# solar_tester.net
KiCad netlist of a schematic drawn in EAGLE
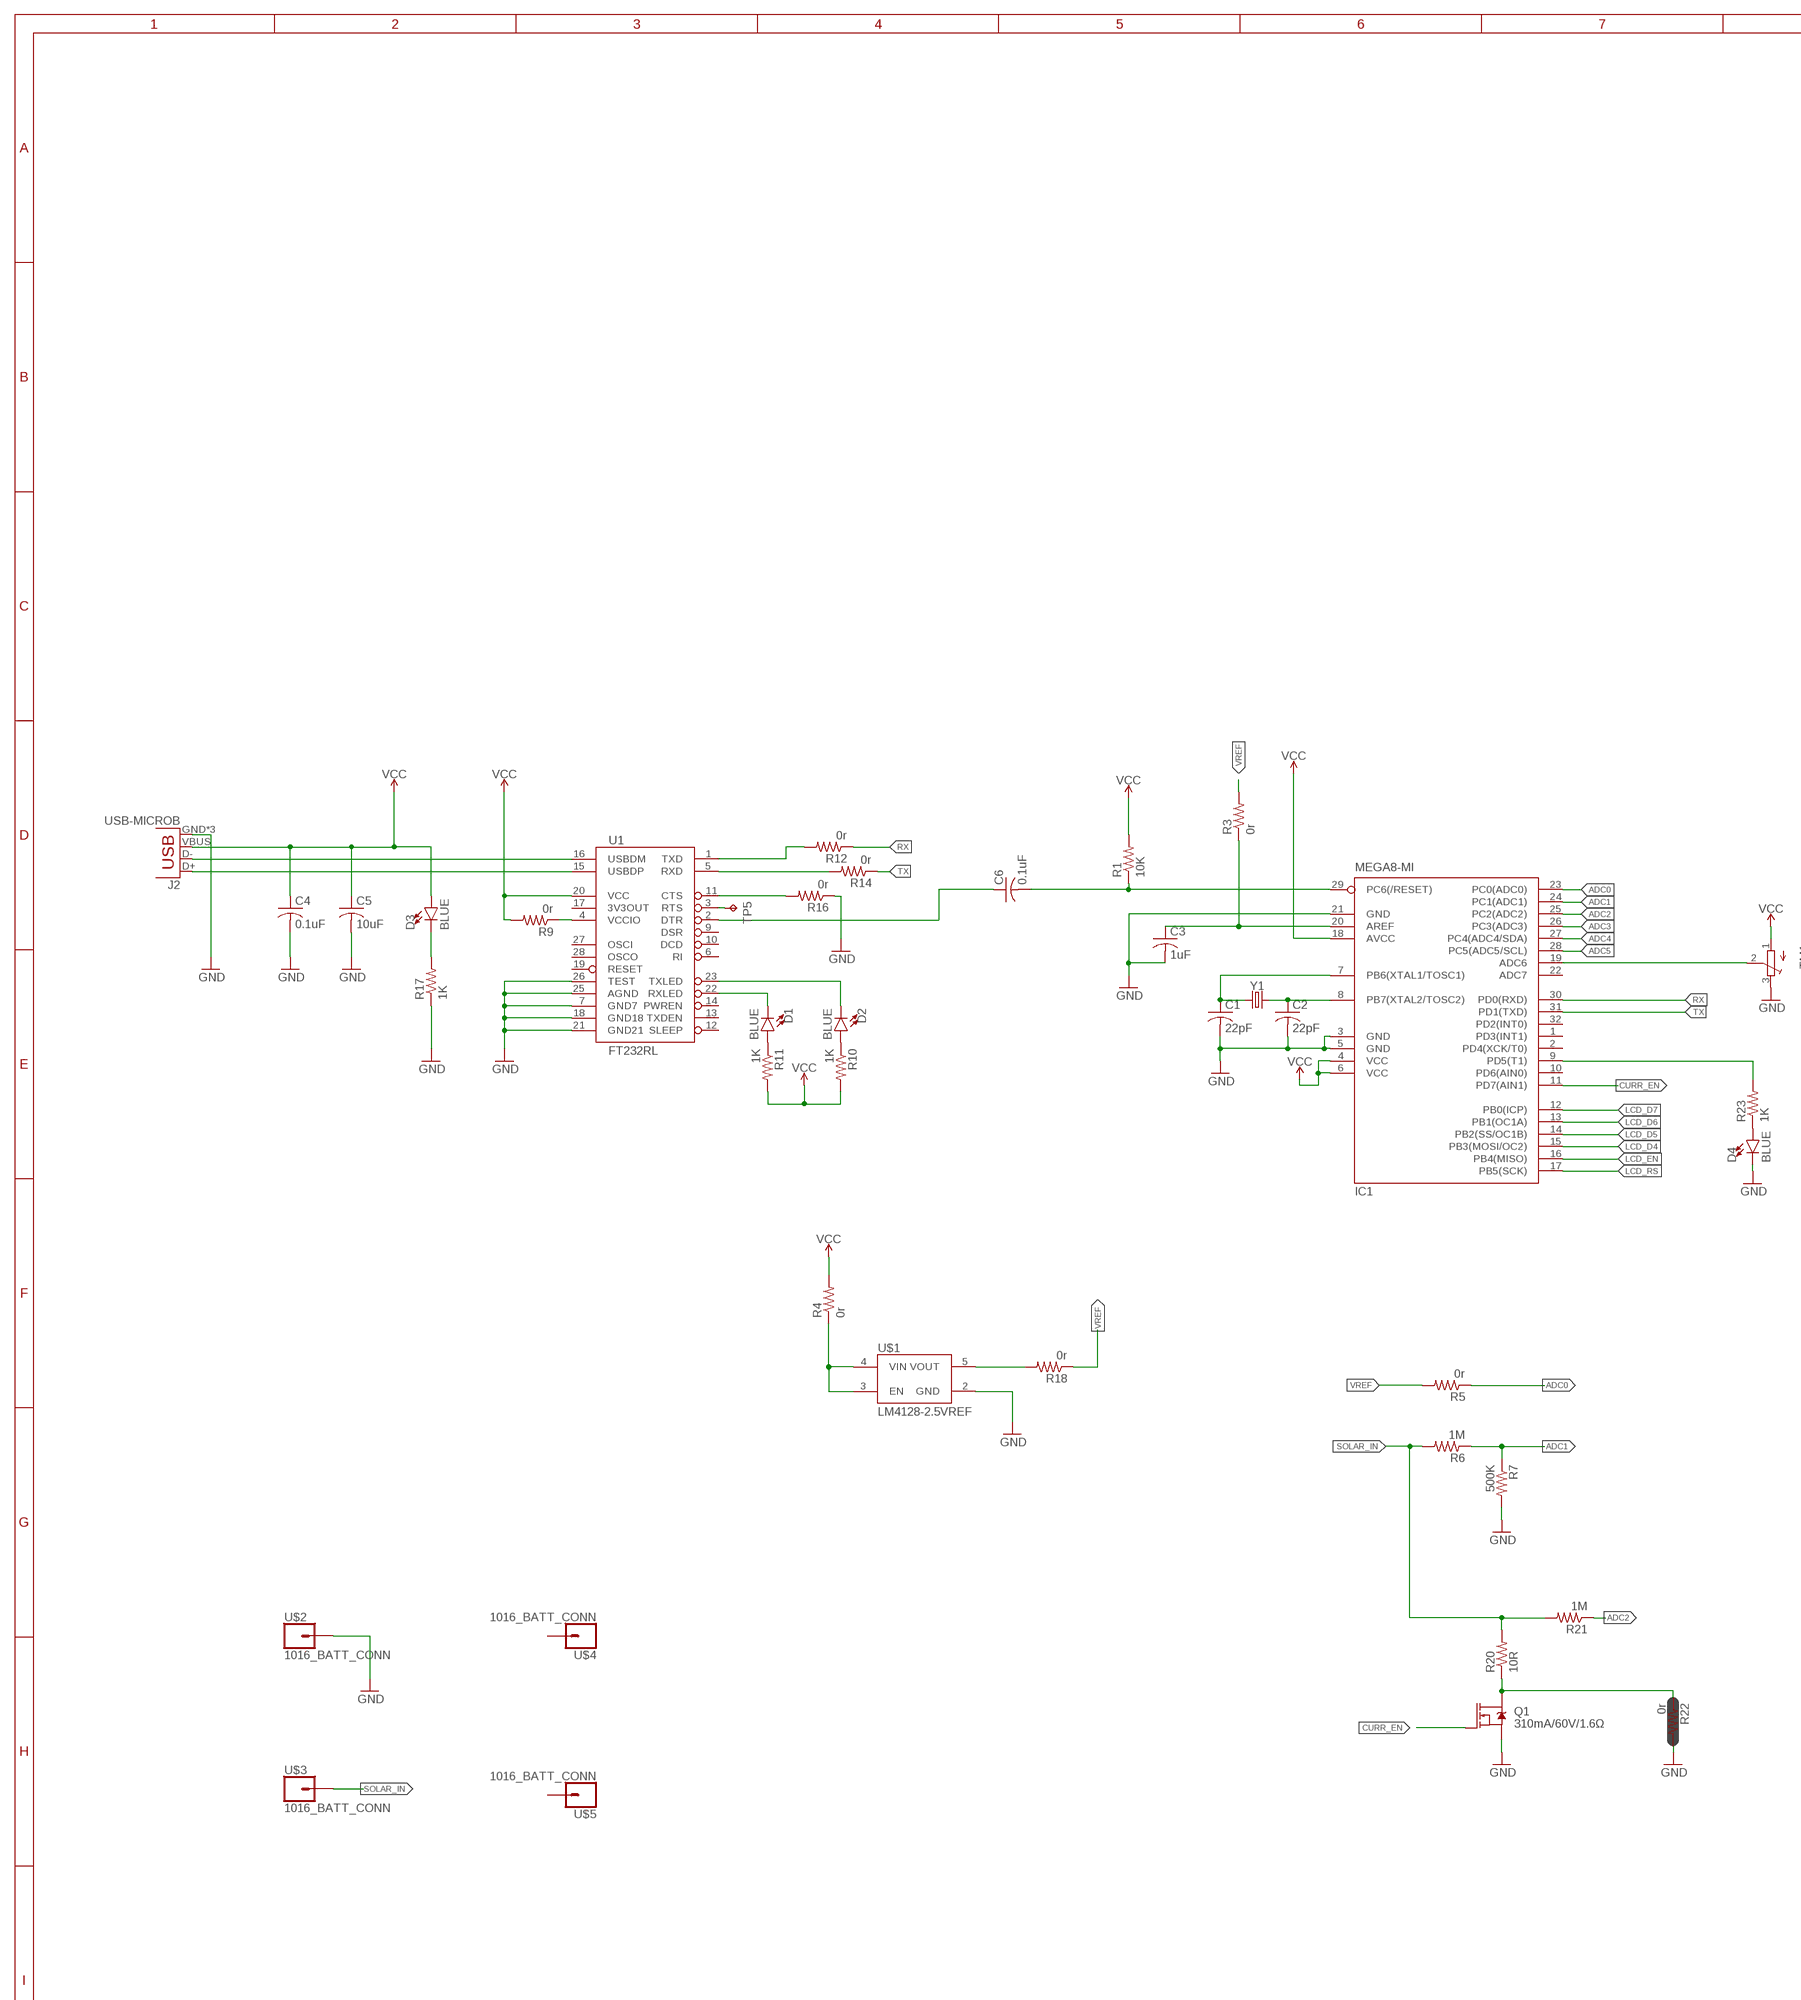
[diagram p0: schematic, sheet 1, part 1 of 2]
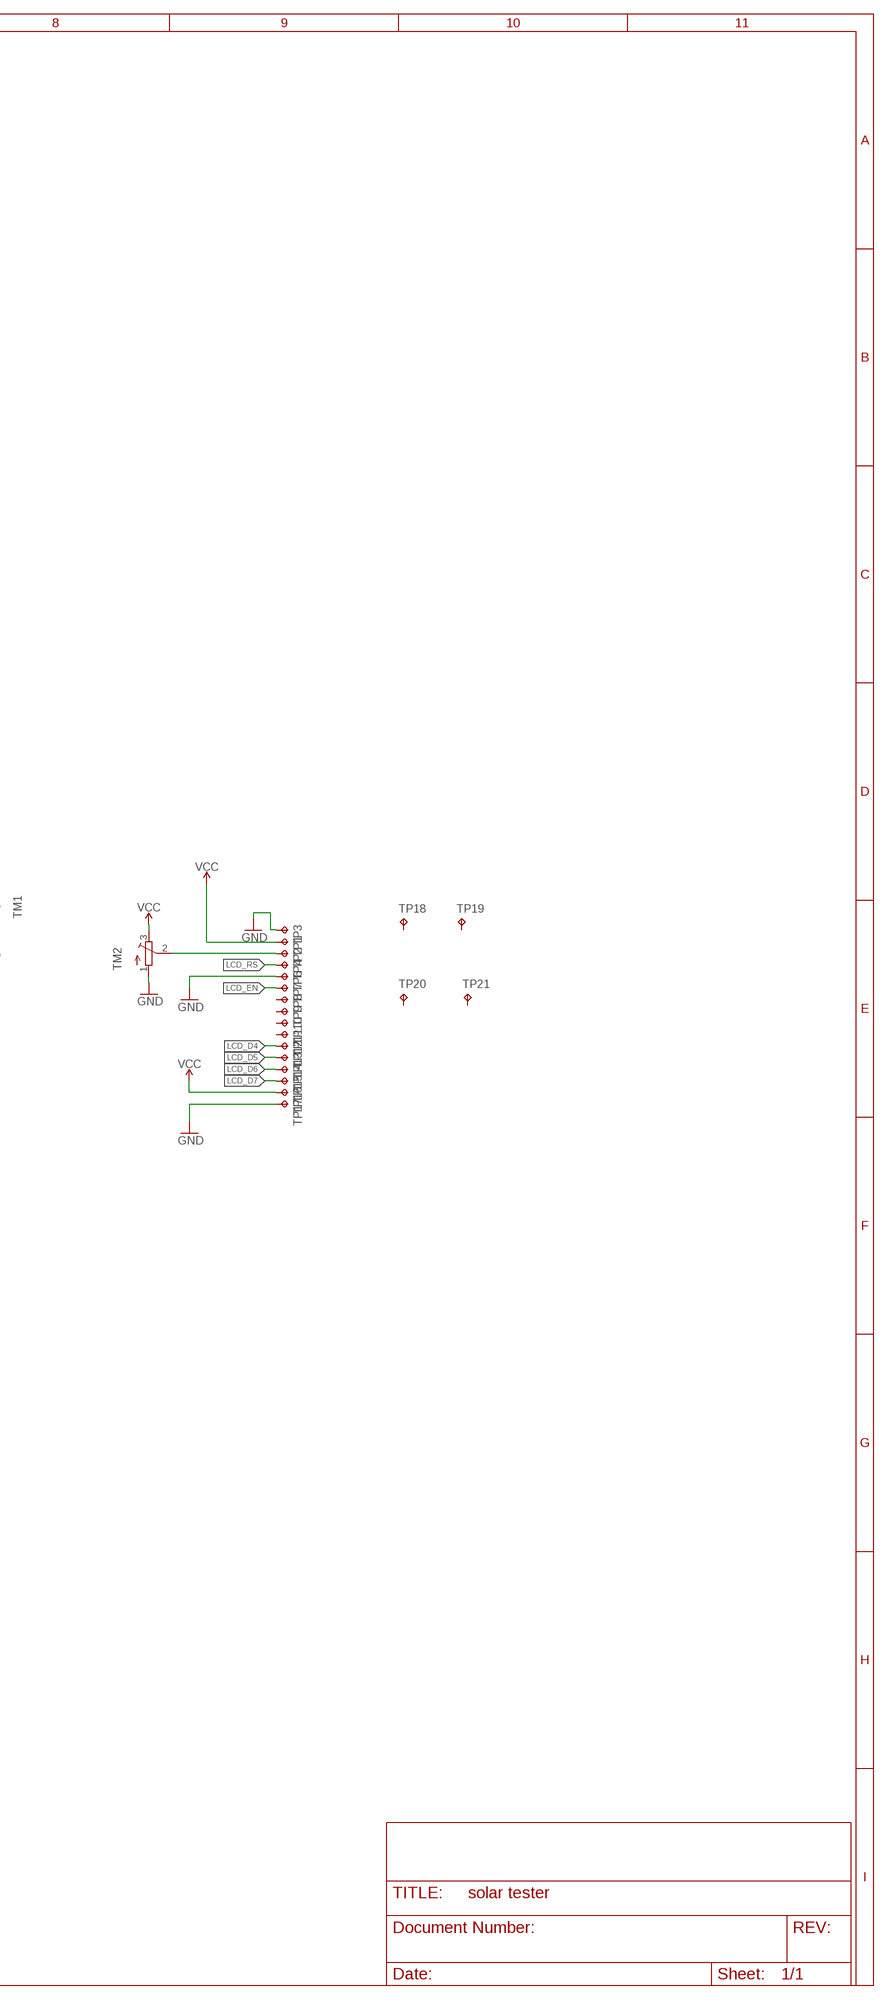
[diagram p1: schematic, sheet 1, part 2 of 2]

(export (version "E")
  (design (tool "Eeschema 10.0.6"))
  (components
    (comp (ref "C1")
      (value "22pF")
      (footprint "eagle-import:C0402")
      (libsource (lib "eagle-import") (part "C-USC0402"))
    )
    (comp (ref "C2")
      (value "22pF")
      (footprint "eagle-import:C0402")
      (libsource (lib "eagle-import") (part "C-USC0402"))
    )
    (comp (ref "C3")
      (value "1uF")
      (footprint "eagle-import:C0402")
      (libsource (lib "eagle-import") (part "C-USC0402"))
    )
    (comp (ref "C4")
      (value "0.1uF")
      (footprint "eagle-import:C0402")
      (libsource (lib "eagle-import") (part "C-USC0402"))
    )
    (comp (ref "C5")
      (value "10uF")
      (footprint "eagle-import:C0402")
      (libsource (lib "eagle-import") (part "C-USC0402"))
    )
    (comp (ref "C6")
      (value "0.1uF")
      (footprint "eagle-import:C0402")
      (libsource (lib "eagle-import") (part "C-USC0402"))
    )
    (comp (ref "D1")
      (value "BLUE")
      (footprint "eagle-import:LED-0603")
      (libsource (lib "eagle-import") (part "LED-BLUE0603"))
    )
    (comp (ref "D2")
      (value "BLUE")
      (footprint "eagle-import:LED-0603")
      (libsource (lib "eagle-import") (part "LED-BLUE0603"))
    )
    (comp (ref "D3")
      (value "BLUE")
      (footprint "eagle-import:LED-0603")
      (libsource (lib "eagle-import") (part "LED-BLUE0603"))
    )
    (comp (ref "D4")
      (value "BLUE")
      (footprint "eagle-import:LED-0603")
      (libsource (lib "eagle-import") (part "LED-BLUE0603"))
    )
    (comp (ref "IC1")
      (value "MEGA8-MI")
      (footprint "eagle-import:MLF32")
      (fields (field (name "MPN") "ATMEGA88PA-MU"))
      (libsource (lib "eagle-import") (part "MEGA8-MI"))
    )
    (comp (ref "J2")
      (value "USB-MICROB")
      (footprint "eagle-import:USB-MICROB")
      (libsource (lib "eagle-import") (part "USB-MICROB"))
    )
    (comp (ref "Q1")
      (value "310mA/60V/1.6Ω")
      (footprint "eagle-import:SOT323")
      (libsource (lib "eagle-import") (part "MOSFET-NCH-2N7002PW"))
    )
    (comp (ref "R1")
      (value "10K")
      (footprint "eagle-import:R0402")
      (libsource (lib "eagle-import") (part "R-US_R0402"))
    )
    (comp (ref "R3")
      (value "0r")
      (footprint "eagle-import:R0402")
      (libsource (lib "eagle-import") (part "R-US_R0402"))
    )
    (comp (ref "R4")
      (value "0r")
      (footprint "eagle-import:R0402")
      (libsource (lib "eagle-import") (part "R-US_R0402"))
    )
    (comp (ref "R5")
      (value "0r")
      (footprint "eagle-import:R0402")
      (libsource (lib "eagle-import") (part "R-US_R0402"))
    )
    (comp (ref "R6")
      (value "1M")
      (footprint "eagle-import:R0402")
      (libsource (lib "eagle-import") (part "R-US_R0402"))
    )
    (comp (ref "R7")
      (value "500K")
      (footprint "eagle-import:R0402")
      (libsource (lib "eagle-import") (part "R-US_R0402"))
    )
    (comp (ref "R9")
      (value "0r")
      (footprint "eagle-import:R0402")
      (libsource (lib "eagle-import") (part "R-US_R0402"))
    )
    (comp (ref "R10")
      (value "1K")
      (footprint "eagle-import:R0402")
      (libsource (lib "eagle-import") (part "R-US_R0402"))
    )
    (comp (ref "R11")
      (value "1K")
      (footprint "eagle-import:R0402")
      (libsource (lib "eagle-import") (part "R-US_R0402"))
    )
    (comp (ref "R12")
      (value "0r")
      (footprint "eagle-import:R0402")
      (libsource (lib "eagle-import") (part "R-US_R0402"))
    )
    (comp (ref "R14")
      (value "0r")
      (footprint "eagle-import:R0402")
      (libsource (lib "eagle-import") (part "R-US_R0402"))
    )
    (comp (ref "R16")
      (value "0r")
      (footprint "eagle-import:R0402")
      (libsource (lib "eagle-import") (part "R-US_R0402"))
    )
    (comp (ref "R17")
      (value "1K")
      (footprint "eagle-import:R0402")
      (libsource (lib "eagle-import") (part "R-US_R0402"))
    )
    (comp (ref "R18")
      (value "0r")
      (footprint "eagle-import:R0402")
      (libsource (lib "eagle-import") (part "R-US_R0402"))
    )
    (comp (ref "R20")
      (value "10R")
      (footprint "eagle-import:M1206")
      (libsource (lib "eagle-import") (part "resistor_R-US_M1206"))
    )
    (comp (ref "R21")
      (value "1M")
      (footprint "eagle-import:R0402")
      (libsource (lib "eagle-import") (part "R-US_R0402"))
    )
    (comp (ref "R22")
      (value "0r")
      (footprint "eagle-import:R0402")
      (libsource (lib "eagle-import") (part "R-US_R0402"))
    )
    (comp (ref "R23")
      (value "1K")
      (footprint "eagle-import:R0402")
      (libsource (lib "eagle-import") (part "R-US_R0402"))
    )
    (comp (ref "TM1")
      (value "TRIMPOTTC33X")
      (footprint "eagle-import:TC33X")
      (libsource (lib "eagle-import") (part "TRIMPOTTC33X"))
    )
    (comp (ref "TM2")
      (value "TRIMPOTTC33X")
      (footprint "eagle-import:TC33X")
      (libsource (lib "eagle-import") (part "TRIMPOTTC33X"))
    )
    (comp (ref "TP1")
      (value "TPTP19R")
      (footprint "eagle-import:TP19R")
      (libsource (lib "eagle-import") (part "TPTP19R"))
    )
    (comp (ref "TP2")
      (value "TPTP19R")
      (footprint "eagle-import:TP19R")
      (libsource (lib "eagle-import") (part "TPTP19R"))
    )
    (comp (ref "TP3")
      (value "TPTP19R")
      (footprint "eagle-import:TP19R")
      (libsource (lib "eagle-import") (part "TPTP19R"))
    )
    (comp (ref "TP4")
      (value "TPTP19R")
      (footprint "eagle-import:TP19R")
      (libsource (lib "eagle-import") (part "TPTP19R"))
    )
    (comp (ref "TP5")
      (value "TPB1,27")
      (footprint "eagle-import:B1,27")
      (libsource (lib "eagle-import") (part "TPB1,27"))
    )
    (comp (ref "TP6")
      (value "TPTP19R")
      (footprint "eagle-import:TP19R")
      (libsource (lib "eagle-import") (part "TPTP19R"))
    )
    (comp (ref "TP7")
      (value "TPTP19R")
      (footprint "eagle-import:TP19R")
      (libsource (lib "eagle-import") (part "TPTP19R"))
    )
    (comp (ref "TP8")
      (value "TPTP19R")
      (footprint "eagle-import:TP19R")
      (libsource (lib "eagle-import") (part "TPTP19R"))
    )
    (comp (ref "TP9")
      (value "TPTP19R")
      (footprint "eagle-import:TP19R")
      (libsource (lib "eagle-import") (part "TPTP19R"))
    )
    (comp (ref "TP10")
      (value "TPTP19R")
      (footprint "eagle-import:TP19R")
      (libsource (lib "eagle-import") (part "TPTP19R"))
    )
    (comp (ref "TP11")
      (value "TPTP19R")
      (footprint "eagle-import:TP19R")
      (libsource (lib "eagle-import") (part "TPTP19R"))
    )
    (comp (ref "TP12")
      (value "TPTP19R")
      (footprint "eagle-import:TP19R")
      (libsource (lib "eagle-import") (part "TPTP19R"))
    )
    (comp (ref "TP13")
      (value "TPTP19R")
      (footprint "eagle-import:TP19R")
      (libsource (lib "eagle-import") (part "TPTP19R"))
    )
    (comp (ref "TP14")
      (value "TPTP19R")
      (footprint "eagle-import:TP19R")
      (libsource (lib "eagle-import") (part "TPTP19R"))
    )
    (comp (ref "TP15")
      (value "TPTP19R")
      (footprint "eagle-import:TP19R")
      (libsource (lib "eagle-import") (part "TPTP19R"))
    )
    (comp (ref "TP16")
      (value "TPTP19R")
      (footprint "eagle-import:TP19R")
      (libsource (lib "eagle-import") (part "TPTP19R"))
    )
    (comp (ref "TP17")
      (value "TPTP19R")
      (footprint "eagle-import:TP19R")
      (libsource (lib "eagle-import") (part "TPTP19R"))
    )
    (comp (ref "TP18")
      (value "TPB2,54")
      (footprint "eagle-import:B2,54")
      (libsource (lib "eagle-import") (part "TPB2,54"))
    )
    (comp (ref "TP19")
      (value "TPB2,54")
      (footprint "eagle-import:B2,54")
      (libsource (lib "eagle-import") (part "TPB2,54"))
    )
    (comp (ref "TP20")
      (value "TPB2,54")
      (footprint "eagle-import:B2,54")
      (libsource (lib "eagle-import") (part "TPB2,54"))
    )
    (comp (ref "TP21")
      (value "TPB2,54")
      (footprint "eagle-import:B2,54")
      (libsource (lib "eagle-import") (part "TPB2,54"))
    )
    (comp (ref "U$1")
      (value "LM4128-2.5VREF")
      (footprint "eagle-import:SOT23-5")
      (libsource (lib "eagle-import") (part "LM4128-2.5VREF"))
    )
    (comp (ref "U$2")
      (value "1016_BATT_CONN")
      (footprint "eagle-import:1016_BATTERY_CONNECTOR")
      (libsource (lib "eagle-import") (part "1016_BATT_CONN"))
    )
    (comp (ref "U$3")
      (value "1016_BATT_CONN")
      (footprint "eagle-import:1016_BATTERY_CONNECTOR")
      (libsource (lib "eagle-import") (part "1016_BATT_CONN"))
    )
    (comp (ref "U$4")
      (value "1016_BATT_CONN")
      (footprint "eagle-import:1016_BATTERY_CONNECTOR")
      (libsource (lib "eagle-import") (part "1016_BATT_CONN"))
    )
    (comp (ref "U$5")
      (value "1016_BATT_CONN")
      (footprint "eagle-import:1016_BATTERY_CONNECTOR")
      (libsource (lib "eagle-import") (part "1016_BATT_CONN"))
    )
    (comp (ref "U1")
      (value "FT232RL")
      (footprint "eagle-import:SSOP28DB")
      (libsource (lib "eagle-import") (part "FT232RLSSOP"))
    )
    (comp (ref "Y1")
      (value "CRYSTALSMD-3.2X2.5")
      (footprint "eagle-import:CRYSTAL-SMD-3.2X2.5MM")
      (libsource (lib "eagle-import") (part "CRYSTALSMD-3.2X2.5"))
    )
  )
  (nets
    (net (code "1") (name "ADC0") (class "Default")
      (node (ref "IC1") (pin "23") (pinfunction "PC0(ADC0)_23") (pintype "bidirectional"))
      (node (ref "R5") (pin "1") (pinfunction "1_1") (pintype "passive"))
    )
    (net (code "2") (name "ADC1") (class "Default")
      (node (ref "IC1") (pin "24") (pinfunction "PC1(ADC1)_24") (pintype "bidirectional"))
      (node (ref "R6") (pin "1") (pinfunction "1_1") (pintype "passive"))
      (node (ref "R7") (pin "1") (pinfunction "1_1") (pintype "passive"))
    )
    (net (code "3") (name "ADC2") (class "Default")
      (node (ref "IC1") (pin "25") (pinfunction "PC2(ADC2)_25") (pintype "bidirectional"))
      (node (ref "R21") (pin "1") (pinfunction "1_1") (pintype "passive"))
    )
    (net (code "4") (name "ADC3") (class "Default")
      (node (ref "IC1") (pin "26") (pinfunction "PC3(ADC3)_26") (pintype "bidirectional"))
    )
    (net (code "5") (name "ADC4") (class "Default")
      (node (ref "IC1") (pin "27") (pinfunction "PC4(ADC4/SDA)_27") (pintype "bidirectional"))
    )
    (net (code "6") (name "ADC5") (class "Default")
      (node (ref "IC1") (pin "28") (pinfunction "PC5(ADC5/SCL)_28") (pintype "bidirectional"))
    )
    (net (code "7") (name "CURR_EN") (class "Default")
      (node (ref "IC1") (pin "11") (pinfunction "PD7(AIN1)_11") (pintype "bidirectional"))
      (node (ref "Q1") (pin "1") (pinfunction "G_1") (pintype "bidirectional"))
    )
    (net (code "8") (name "GND") (class "Default")
      (node (ref "C1") (pin "2") (pinfunction "2_2") (pintype "passive"))
      (node (ref "C2") (pin "2") (pinfunction "2_2") (pintype "passive"))
      (node (ref "C3") (pin "2") (pinfunction "2_2") (pintype "passive"))
      (node (ref "C4") (pin "2") (pinfunction "2_2") (pintype "passive"))
      (node (ref "C5") (pin "2") (pinfunction "2_2") (pintype "passive"))
      (node (ref "D4") (pin "C") (pinfunction "C_C") (pintype "passive"))
      (node (ref "IC1") (pin "21") (pinfunction "GND_21") (pintype "power_in"))
      (node (ref "IC1") (pin "3") (pinfunction "GND_3") (pintype "power_in"))
      (node (ref "IC1") (pin "5") (pinfunction "GND_5") (pintype "power_in"))
      (node (ref "J2") (pin "GND") (pinfunction "GND_GND") (pintype "bidirectional"))
      (node (ref "J2") (pin "MT1") (pinfunction "GND_MT1") (pintype "bidirectional"))
      (node (ref "J2") (pin "MT2") (pinfunction "GND_MT2") (pintype "bidirectional"))
      (node (ref "Q1") (pin "2") (pinfunction "S_2") (pintype "bidirectional"))
      (node (ref "R16") (pin "1") (pinfunction "1_1") (pintype "passive"))
      (node (ref "R17") (pin "1") (pinfunction "1_1") (pintype "passive"))
      (node (ref "R22") (pin "2") (pinfunction "2_2") (pintype "passive"))
      (node (ref "R7") (pin "2") (pinfunction "2_2") (pintype "passive"))
      (node (ref "TM1") (pin "3") (pinfunction "E_3") (pintype "passive"))
      (node (ref "TM2") (pin "1") (pinfunction "A_1") (pintype "passive"))
      (node (ref "TP17") (pin "TP") (pinfunction "TP_TP") (pintype "input"))
      (node (ref "TP3") (pin "TP") (pinfunction "TP_TP") (pintype "input"))
      (node (ref "TP6") (pin "TP") (pinfunction "TP_TP") (pintype "input"))
      (node (ref "U$1") (pin "2") (pinfunction "GND_2") (pintype "bidirectional"))
      (node (ref "U$2") (pin "P$1") (pinfunction "1_P$1") (pintype "passive"))
      (node (ref "U1") (pin "18") (pinfunction "GND18_18") (pintype "power_in"))
      (node (ref "U1") (pin "21") (pinfunction "GND21_21") (pintype "power_in"))
      (node (ref "U1") (pin "25") (pinfunction "AGND_25") (pintype "power_in"))
      (node (ref "U1") (pin "26") (pinfunction "TEST_26") (pintype "input"))
      (node (ref "U1") (pin "7") (pinfunction "GND7_7") (pintype "power_in"))
    )
    (net (code "9") (name "LCD_D4") (class "Default")
      (node (ref "IC1") (pin "15") (pinfunction "PB3(MOSI/OC2)_15") (pintype "bidirectional"))
      (node (ref "TP12") (pin "TP") (pinfunction "TP_TP") (pintype "input"))
    )
    (net (code "10") (name "LCD_D5") (class "Default")
      (node (ref "IC1") (pin "14") (pinfunction "PB2(SS/OC1B)_14") (pintype "bidirectional"))
      (node (ref "TP13") (pin "TP") (pinfunction "TP_TP") (pintype "input"))
    )
    (net (code "11") (name "LCD_D6") (class "Default")
      (node (ref "IC1") (pin "13") (pinfunction "PB1(OC1A)_13") (pintype "bidirectional"))
      (node (ref "TP14") (pin "TP") (pinfunction "TP_TP") (pintype "input"))
    )
    (net (code "12") (name "LCD_D7") (class "Default")
      (node (ref "IC1") (pin "12") (pinfunction "PB0(ICP)_12") (pintype "bidirectional"))
      (node (ref "TP15") (pin "TP") (pinfunction "TP_TP") (pintype "input"))
    )
    (net (code "13") (name "LCD_EN") (class "Default")
      (node (ref "IC1") (pin "16") (pinfunction "PB4(MISO)_16") (pintype "bidirectional"))
      (node (ref "TP7") (pin "TP") (pinfunction "TP_TP") (pintype "input"))
    )
    (net (code "14") (name "LCD_RS") (class "Default")
      (node (ref "IC1") (pin "17") (pinfunction "PB5(SCK)_17") (pintype "bidirectional"))
      (node (ref "TP4") (pin "TP") (pinfunction "TP_TP") (pintype "input"))
    )
    (net (code "15") (name "Net-(D1-PadA)") (class "Default")
      (node (ref "D1") (pin "A") (pinfunction "A_A") (pintype "passive"))
      (node (ref "R11") (pin "1") (pinfunction "1_1") (pintype "passive"))
    )
    (net (code "16") (name "Net-(D2-PadA)") (class "Default")
      (node (ref "D2") (pin "A") (pinfunction "A_A") (pintype "passive"))
      (node (ref "R10") (pin "1") (pinfunction "1_1") (pintype "passive"))
    )
    (net (code "17") (name "Net-(D3-PadC)") (class "Default")
      (node (ref "D3") (pin "C") (pinfunction "C_C") (pintype "passive"))
      (node (ref "R17") (pin "2") (pinfunction "2_2") (pintype "passive"))
    )
    (net (code "18") (name "Net-(D4-PadA)") (class "Default")
      (node (ref "D4") (pin "A") (pinfunction "A_A") (pintype "passive"))
      (node (ref "R23") (pin "1") (pinfunction "1_1") (pintype "passive"))
    )
    (net (code "19") (name "Net-(IC1-ADC6)") (class "Default")
      (node (ref "IC1") (pin "19") (pinfunction "ADC6_19") (pintype "bidirectional"))
      (node (ref "TM1") (pin "2") (pinfunction "S_2") (pintype "passive"))
    )
    (net (code "20") (name "Net-(IC1-AREF)") (class "Default")
      (node (ref "C3") (pin "1") (pinfunction "1_1") (pintype "passive"))
      (node (ref "IC1") (pin "20") (pinfunction "AREF_20") (pintype "passive"))
      (node (ref "R3") (pin "1") (pinfunction "1_1") (pintype "passive"))
    )
    (net (code "21") (name "Net-(IC1-PB6(XTAL1{slash}TOSC1))") (class "Default")
      (node (ref "C1") (pin "1") (pinfunction "1_1") (pintype "passive"))
      (node (ref "IC1") (pin "7") (pinfunction "PB6(XTAL1/TOSC1)_7") (pintype "bidirectional"))
      (node (ref "Y1") (pin "1") (pinfunction "1_1") (pintype "passive"))
    )
    (net (code "22") (name "Net-(IC1-PB7(XTAL2{slash}TOSC2))") (class "Default")
      (node (ref "C2") (pin "1") (pinfunction "1_1") (pintype "passive"))
      (node (ref "IC1") (pin "8") (pinfunction "PB7(XTAL2/TOSC2)_8") (pintype "bidirectional"))
      (node (ref "Y1") (pin "3") (pinfunction "2_3") (pintype "passive"))
    )
    (net (code "23") (name "Net-(IC1-PC6({slash}RESET))") (class "Default")
      (node (ref "C6") (pin "2") (pinfunction "2_2") (pintype "passive"))
      (node (ref "IC1") (pin "29") (pinfunction "PC6(/RESET)_29") (pintype "bidirectional"))
      (node (ref "R1") (pin "1") (pinfunction "1_1") (pintype "passive"))
    )
    (net (code "24") (name "Net-(IC1-PD5(T1))") (class "Default")
      (node (ref "IC1") (pin "9") (pinfunction "PD5(T1)_9") (pintype "bidirectional"))
      (node (ref "R23") (pin "2") (pinfunction "2_2") (pintype "passive"))
    )
    (net (code "25") (name "Net-(Q1-D)") (class "Default")
      (node (ref "Q1") (pin "3") (pinfunction "D_3") (pintype "bidirectional"))
      (node (ref "R20") (pin "1") (pinfunction "1_1") (pintype "passive"))
      (node (ref "R22") (pin "1") (pinfunction "1_1") (pintype "passive"))
    )
    (net (code "26") (name "Net-(TM2-S)") (class "Default")
      (node (ref "TM2") (pin "2") (pinfunction "S_2") (pintype "passive"))
      (node (ref "TP2") (pin "TP") (pinfunction "TP_TP") (pintype "input"))
    )
    (net (code "27") (name "Net-(U$1-EN)") (class "Default")
      (node (ref "R4") (pin "1") (pinfunction "1_1") (pintype "passive"))
      (node (ref "U$1") (pin "3") (pinfunction "EN_3") (pintype "bidirectional"))
      (node (ref "U$1") (pin "4") (pinfunction "VIN_4") (pintype "bidirectional"))
    )
    (net (code "28") (name "Net-(U$1-VOUT)") (class "Default")
      (node (ref "R18") (pin "2") (pinfunction "2_2") (pintype "passive"))
      (node (ref "U$1") (pin "5") (pinfunction "VOUT_5") (pintype "bidirectional"))
    )
    (net (code "29") (name "Net-(U1-CTS)") (class "Default")
      (node (ref "R16") (pin "2") (pinfunction "2_2") (pintype "passive"))
      (node (ref "U1") (pin "11") (pinfunction "CTS_11") (pintype "input"))
    )
    (net (code "30") (name "Net-(U1-DTR)") (class "Default")
      (node (ref "C6") (pin "1") (pinfunction "1_1") (pintype "passive"))
      (node (ref "U1") (pin "2") (pinfunction "DTR_2") (pintype "output"))
    )
    (net (code "31") (name "Net-(U1-RTS)") (class "Default")
      (node (ref "TP5") (pin "TP") (pinfunction "TP_TP") (pintype "input"))
      (node (ref "U1") (pin "3") (pinfunction "RTS_3") (pintype "output"))
    )
    (net (code "32") (name "Net-(U1-RXD)") (class "Default")
      (node (ref "R14") (pin "2") (pinfunction "2_2") (pintype "passive"))
      (node (ref "U1") (pin "5") (pinfunction "RXD_5") (pintype "input"))
    )
    (net (code "33") (name "Net-(U1-RXLED)") (class "Default")
      (node (ref "D1") (pin "C") (pinfunction "C_C") (pintype "passive"))
      (node (ref "U1") (pin "22") (pinfunction "RXLED_22") (pintype "input"))
    )
    (net (code "34") (name "Net-(U1-TXD)") (class "Default")
      (node (ref "R12") (pin "2") (pinfunction "2_2") (pintype "passive"))
      (node (ref "U1") (pin "1") (pinfunction "TXD_1") (pintype "output"))
    )
    (net (code "35") (name "Net-(U1-TXLED)") (class "Default")
      (node (ref "D2") (pin "C") (pinfunction "C_C") (pintype "passive"))
      (node (ref "U1") (pin "23") (pinfunction "TXLED_23") (pintype "input"))
    )
    (net (code "36") (name "Net-(U1-USBDM)") (class "Default")
      (node (ref "J2") (pin "D-") (pinfunction "D-_D-") (pintype "bidirectional"))
      (node (ref "U1") (pin "16") (pinfunction "USBDM_16") (pintype "bidirectional"))
    )
    (net (code "37") (name "Net-(U1-USBDP)") (class "Default")
      (node (ref "J2") (pin "D+") (pinfunction "D+_D+") (pintype "bidirectional"))
      (node (ref "U1") (pin "15") (pinfunction "USBDP_15") (pintype "bidirectional"))
    )
    (net (code "38") (name "Net-(U1-VCCIO)") (class "Default")
      (node (ref "R9") (pin "1") (pinfunction "1_1") (pintype "passive"))
      (node (ref "U1") (pin "4") (pinfunction "VCCIO_4") (pintype "power_in"))
    )
    (net (code "39") (name "RX") (class "Default")
      (node (ref "IC1") (pin "30") (pinfunction "PD0(RXD)_30") (pintype "bidirectional"))
      (node (ref "R12") (pin "1") (pinfunction "1_1") (pintype "passive"))
    )
    (net (code "40") (name "SOLAR_IN") (class "Default")
      (node (ref "R20") (pin "2") (pinfunction "2_2") (pintype "passive"))
      (node (ref "R21") (pin "2") (pinfunction "2_2") (pintype "passive"))
      (node (ref "R6") (pin "2") (pinfunction "2_2") (pintype "passive"))
      (node (ref "U$3") (pin "P$1") (pinfunction "1_P$1") (pintype "passive"))
    )
    (net (code "41") (name "TX") (class "Default")
      (node (ref "IC1") (pin "31") (pinfunction "PD1(TXD)_31") (pintype "bidirectional"))
      (node (ref "R14") (pin "1") (pinfunction "1_1") (pintype "passive"))
    )
    (net (code "42") (name "VCC") (class "Default")
      (node (ref "C4") (pin "1") (pinfunction "1_1") (pintype "passive"))
      (node (ref "C5") (pin "1") (pinfunction "1_1") (pintype "passive"))
      (node (ref "D3") (pin "A") (pinfunction "A_A") (pintype "passive"))
      (node (ref "IC1") (pin "18") (pinfunction "AVCC_18") (pintype "power_in"))
      (node (ref "IC1") (pin "4") (pinfunction "VCC_4") (pintype "power_in"))
      (node (ref "IC1") (pin "6") (pinfunction "VCC_6") (pintype "power_in"))
      (node (ref "J2") (pin "VBUS") (pinfunction "VBUS_VBUS") (pintype "bidirectional"))
      (node (ref "R1") (pin "2") (pinfunction "2_2") (pintype "passive"))
      (node (ref "R10") (pin "2") (pinfunction "2_2") (pintype "passive"))
      (node (ref "R11") (pin "2") (pinfunction "2_2") (pintype "passive"))
      (node (ref "R4") (pin "2") (pinfunction "2_2") (pintype "passive"))
      (node (ref "R9") (pin "2") (pinfunction "2_2") (pintype "passive"))
      (node (ref "TM1") (pin "1") (pinfunction "A_1") (pintype "passive"))
      (node (ref "TM2") (pin "3") (pinfunction "E_3") (pintype "passive"))
      (node (ref "TP1") (pin "TP") (pinfunction "TP_TP") (pintype "input"))
      (node (ref "TP16") (pin "TP") (pinfunction "TP_TP") (pintype "input"))
      (node (ref "U1") (pin "20") (pinfunction "VCC_20") (pintype "power_in"))
    )
    (net (code "43") (name "VREF") (class "Default")
      (node (ref "R18") (pin "1") (pinfunction "1_1") (pintype "passive"))
      (node (ref "R3") (pin "2") (pinfunction "2_2") (pintype "passive"))
      (node (ref "R5") (pin "2") (pinfunction "2_2") (pintype "passive"))
    )
    (net (code "44") (name "unconnected-(IC1-ADC7-Pad22)") (class "Default")
      (node (ref "IC1") (pin "22") (pinfunction "ADC7_22") (pintype "bidirectional"))
    )
    (net (code "45") (name "unconnected-(IC1-PD2(INT0)-Pad32)") (class "Default")
      (node (ref "IC1") (pin "32") (pinfunction "PD2(INT0)_32") (pintype "bidirectional"))
    )
    (net (code "46") (name "unconnected-(IC1-PD3(INT1)-Pad1)") (class "Default")
      (node (ref "IC1") (pin "1") (pinfunction "PD3(INT1)_1") (pintype "bidirectional"))
    )
    (net (code "47") (name "unconnected-(IC1-PD4(XCK{slash}T0)-Pad2)") (class "Default")
      (node (ref "IC1") (pin "2") (pinfunction "PD4(XCK/T0)_2") (pintype "bidirectional"))
    )
    (net (code "48") (name "unconnected-(IC1-PD6(AIN0)-Pad10)") (class "Default")
      (node (ref "IC1") (pin "10") (pinfunction "PD6(AIN0)_10") (pintype "bidirectional"))
    )
    (net (code "49") (name "unconnected-(TP8-PadTP)") (class "Default")
      (node (ref "TP8") (pin "TP") (pinfunction "TP_TP") (pintype "input"))
    )
    (net (code "50") (name "unconnected-(TP9-PadTP)") (class "Default")
      (node (ref "TP9") (pin "TP") (pinfunction "TP_TP") (pintype "input"))
    )
    (net (code "51") (name "unconnected-(TP10-PadTP)") (class "Default")
      (node (ref "TP10") (pin "TP") (pinfunction "TP_TP") (pintype "input"))
    )
    (net (code "52") (name "unconnected-(TP11-PadTP)") (class "Default")
      (node (ref "TP11") (pin "TP") (pinfunction "TP_TP") (pintype "input"))
    )
    (net (code "53") (name "unconnected-(TP18-PadTP)") (class "Default")
      (node (ref "TP18") (pin "TP") (pinfunction "TP_TP") (pintype "input"))
    )
    (net (code "54") (name "unconnected-(TP19-PadTP)") (class "Default")
      (node (ref "TP19") (pin "TP") (pinfunction "TP_TP") (pintype "input"))
    )
    (net (code "55") (name "unconnected-(TP20-PadTP)") (class "Default")
      (node (ref "TP20") (pin "TP") (pinfunction "TP_TP") (pintype "input"))
    )
    (net (code "56") (name "unconnected-(TP21-PadTP)") (class "Default")
      (node (ref "TP21") (pin "TP") (pinfunction "TP_TP") (pintype "input"))
    )
    (net (code "57") (name "unconnected-(U$4-1-PadP$1)") (class "Default")
      (node (ref "U$4") (pin "P$1") (pinfunction "1_P$1") (pintype "passive"))
    )
    (net (code "58") (name "unconnected-(U$5-1-PadP$1)") (class "Default")
      (node (ref "U$5") (pin "P$1") (pinfunction "1_P$1") (pintype "passive"))
    )
    (net (code "59") (name "unconnected-(U1-3V3OUT-Pad17)") (class "Default")
      (node (ref "U1") (pin "17") (pinfunction "3V3OUT_17") (pintype "output"))
    )
    (net (code "60") (name "unconnected-(U1-DCD-Pad10)") (class "Default")
      (node (ref "U1") (pin "10") (pinfunction "DCD_10") (pintype "input"))
    )
    (net (code "61") (name "unconnected-(U1-DSR-Pad9)") (class "Default")
      (node (ref "U1") (pin "9") (pinfunction "DSR_9") (pintype "input"))
    )
    (net (code "62") (name "unconnected-(U1-OSCI-Pad27)") (class "Default")
      (node (ref "U1") (pin "27") (pinfunction "OSCI_27") (pintype "input"))
    )
    (net (code "63") (name "unconnected-(U1-OSCO-Pad28)") (class "Default")
      (node (ref "U1") (pin "28") (pinfunction "OSCO_28") (pintype "output"))
    )
    (net (code "64") (name "unconnected-(U1-PWREN-Pad14)") (class "Default")
      (node (ref "U1") (pin "14") (pinfunction "PWREN_14") (pintype "input"))
    )
    (net (code "65") (name "unconnected-(U1-RESET-Pad19)") (class "Default")
      (node (ref "U1") (pin "19") (pinfunction "RESET_19") (pintype "input"))
    )
    (net (code "66") (name "unconnected-(U1-RI-Pad6)") (class "Default")
      (node (ref "U1") (pin "6") (pinfunction "RI_6") (pintype "input"))
    )
    (net (code "67") (name "unconnected-(U1-SLEEP-Pad12)") (class "Default")
      (node (ref "U1") (pin "12") (pinfunction "SLEEP_12") (pintype "input"))
    )
    (net (code "68") (name "unconnected-(U1-TXDEN-Pad13)") (class "Default")
      (node (ref "U1") (pin "13") (pinfunction "TXDEN_13") (pintype "input"))
    )
  )
)
